# sterio_mic_MCU.net
KiCad netlist of a schematic drawn in Altium Designer
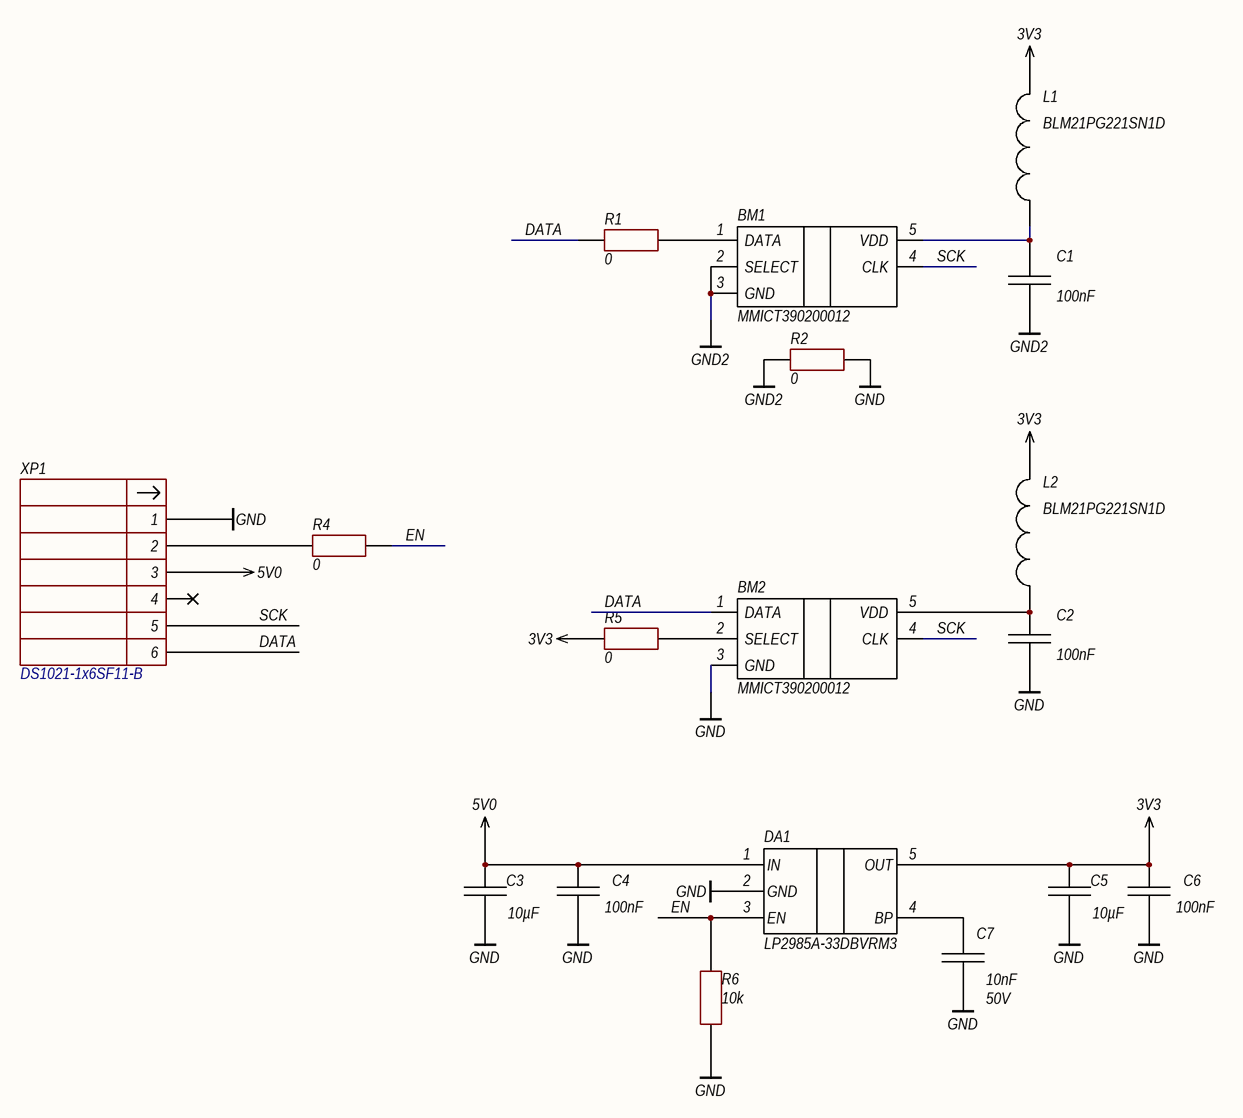
[diagram p0: sterio_mic MCU.SchDoc]

(export (version "E")
  (design (tool "Eeschema 10.0.6"))
  (components
    (comp (ref "BM1")
      (value "MMICT390200012")
      (footprint "5-Terminal LGA_CAV")
      (description "digital MEMS microphone")
      (fields (field (name "MANUFACTURER") "TDK") (field (name "AUTHOR") "t.dorakh"))
      (libsource (lib "EnCata Concord Pro") (part "MMICT390200012"))
    )
    (comp (ref "BM2")
      (value "MMICT390200012")
      (footprint "5-Terminal LGA_CAV")
      (description "digital MEMS microphone")
      (fields (field (name "MANUFACTURER") "TDK") (field (name "AUTHOR") "t.dorakh"))
      (libsource (lib "EnCata Concord Pro") (part "MMICT390200012"))
    )
    (comp (ref "C1")
      (value "CC0805KPX7R9BB104")
      (footprint "CAPC0805_H0.95_N")
      (description "0805 100nF 50V ±10% X7R")
      (fields
        (field (name "TOLERANCE") "10%")
        (field (name "CAPACITANCE") "100nF")
        (field (name "MANUFACTURER") "Yageo")
        (field (name "AUTHOR") "m.seliadtsou")
      )
      (libsource (lib "EnCata Concord Pro") (part "C"))
    )
    (comp (ref "C2")
      (value "CC0805KPX7R9BB104")
      (footprint "CAPC0805_H0.95_N")
      (description "0805 100nF 50V ±10% X7R")
      (fields
        (field (name "TOLERANCE") "10%")
        (field (name "CAPACITANCE") "100nF")
        (field (name "MANUFACTURER") "Yageo")
        (field (name "AUTHOR") "m.seliadtsou")
      )
      (libsource (lib "EnCata Concord Pro") (part "C"))
    )
    (comp (ref "C3")
      (value "CL21B106KOQNNNE")
      (footprint "CAPC0805_H1.45_N")
      (description "0805 10uF 16V ±10% X7R")
      (fields
        (field (name "CAPACITANCE") "10µF")
        (field (name "MANUFACTURER") "Samsung Electro-Mechanics")
        (field (name "TOLERANCE") "10%")
        (field (name "AUTHOR") "m.boltromeyuk")
      )
      (libsource (lib "EnCata Concord Pro") (part "C"))
    )
    (comp (ref "C4")
      (value "CC0805KPX7R9BB104")
      (footprint "CAPC0805_H0.95_N")
      (description "0805 100nF 50V ±10% X7R")
      (fields
        (field (name "TOLERANCE") "10%")
        (field (name "CAPACITANCE") "100nF")
        (field (name "MANUFACTURER") "Yageo")
        (field (name "AUTHOR") "m.seliadtsou")
      )
      (libsource (lib "EnCata Concord Pro") (part "C"))
    )
    (comp (ref "C5")
      (value "CL21B106KOQNNNE")
      (footprint "CAPC0805_H1.45_N")
      (description "0805 10uF 16V ±10% X7R")
      (fields
        (field (name "CAPACITANCE") "10µF")
        (field (name "MANUFACTURER") "Samsung Electro-Mechanics")
        (field (name "TOLERANCE") "10%")
        (field (name "AUTHOR") "m.boltromeyuk")
      )
      (libsource (lib "EnCata Concord Pro") (part "C"))
    )
    (comp (ref "C6")
      (value "CC0805KPX7R9BB104")
      (footprint "CAPC0805_H0.95_N")
      (description "0805 100nF 50V ±10% X7R")
      (fields
        (field (name "TOLERANCE") "10%")
        (field (name "CAPACITANCE") "100nF")
        (field (name "MANUFACTURER") "Yageo")
        (field (name "AUTHOR") "m.seliadtsou")
      )
      (libsource (lib "EnCata Concord Pro") (part "C"))
    )
    (comp (ref "C7")
      (value "CC0805JKNPO9BN103")
      (footprint "CAPC0805_H0.95_N")
      (description "0805 10nF 50V ±5% NP0")
      (fields
        (field (name "CAPACITANCE") "10nF")
        (field (name "MANUFACTURER") "Yageo")
        (field (name "TOLERANCE") "5%")
        (field (name "VOLTAGE RATING") "50V")
        (field (name "AUTHOR") "v.ivanchenko")
      )
      (libsource (lib "EnCata Concord Pro") (part "C"))
    )
    (comp (ref "DA1")
      (value "LP2985A-33DBVRM3")
      (footprint "SOT-23-5")
      (description "150-mA 16-V low-dropout (LDO) voltage regulator with high-accuracy 5-SOT-23 -40 to 125")
      (fields (field (name "MANUFACTURER") "Texas Instruments") (field (name "AUTHOR") "i.auramchyk"))
      (libsource (lib "EnCata Concord Pro") (part "LP2985A"))
    )
    (comp (ref "L1")
      (value "BLM21PG221SN1D")
      (footprint "INDC0805_H1.25_N")
      (description "9mΩ ±25% 22Ω@100MHz 6A 0805 Ferrite Beads ROHS")
      (fields
        (field (name "MANUFACTURER") "Murata Electronics")
        (field (name "MANUFACTURER PART NUMBER") "BLM21PG220SN1D")
        (field (name "AUTHOR") "m.boltromeyuk")
      )
      (libsource (lib "EnCata Concord Pro") (part "L"))
    )
    (comp (ref "L2")
      (value "BLM21PG221SN1D")
      (footprint "INDC0805_H1.25_N")
      (description "9mΩ ±25% 22Ω@100MHz 6A 0805 Ferrite Beads ROHS")
      (fields
        (field (name "MANUFACTURER") "Murata Electronics")
        (field (name "MANUFACTURER PART NUMBER") "BLM21PG220SN1D")
        (field (name "AUTHOR") "m.boltromeyuk")
      )
      (libsource (lib "EnCata Concord Pro") (part "L"))
    )
    (comp (ref "R1")
      (value "RC0805FR-070RL")
      (footprint "RESC0805_N")
      (description "RES SMD 0 OHM JUMPER 1% 1/8W 0805")
      (fields
        (field (name "MANUFACTURER") "Yageo")
        (field (name "RESISTANCE") "0")
        (field (name "TOLERANCE") "1%")
        (field (name "AUTHOR") "M.S. Koval")
      )
      (libsource (lib "") (part "R_GENERAL_2"))
    )
    (comp (ref "R2")
      (value "RC0805FR-070RL")
      (footprint "RESC0805_N")
      (description "RES SMD 0 OHM JUMPER 1% 1/8W 0805")
      (fields
        (field (name "MANUFACTURER") "Yageo")
        (field (name "RESISTANCE") "0")
        (field (name "TOLERANCE") "1%")
        (field (name "AUTHOR") "M.S. Koval")
      )
      (libsource (lib "EnCata Concord Pro") (part "R_GENERAL"))
    )
    (comp (ref "R4")
      (value "RC0805FR-070RL")
      (footprint "RESC0805_N")
      (description "RES SMD 0 OHM JUMPER 1% 1/8W 0805")
      (fields
        (field (name "MANUFACTURER") "Yageo")
        (field (name "RESISTANCE") "0")
        (field (name "TOLERANCE") "1%")
        (field (name "AUTHOR") "M.S. Koval")
      )
      (libsource (lib "EnCata Concord Pro") (part "R_GENERAL"))
    )
    (comp (ref "R5")
      (value "RC0805FR-070RL")
      (footprint "RESC0805_N")
      (description "RES SMD 0 OHM JUMPER 1% 1/8W 0805")
      (fields
        (field (name "MANUFACTURER") "Yageo")
        (field (name "RESISTANCE") "0")
        (field (name "TOLERANCE") "1%")
        (field (name "AUTHOR") "M.S. Koval")
      )
      (libsource (lib "") (part "R_GENERAL_2"))
    )
    (comp (ref "R6")
      (value "RT0805BRB0710KL")
      (footprint "RESC0805_N")
      (description "RES SMD 10 KOHM 0.1% 1/8W 0805  10ppm")
      (fields
        (field (name "MANUFACTURER") "Yageo")
        (field (name "RESISTANCE") "10k")
        (field (name "TOLERANCE") "0.1%")
        (field (name "AUTHOR") "u.sushko")
      )
      (libsource (lib "") (part "R_GENERAL_1"))
    )
    (comp (ref "XP1")
      (value "DS1021-1x6SF11-B")
      (footprint "PLS-6(DS-1021-1x6)")
      (description "2.54mm, 6 pin, Male, 3A, Vertical mounting, CONNFLY")
      (fields (field (name "MANUFACTURER") "CONNFLY") (field (name "AUTHOR") "a.antipov"))
      (libsource (lib "EnCata Concord Pro") (part "XP6"))
    )
  )
  (nets
    (net (code "1") (name "/DATA") (class "Default")
      (node (ref "BM2") (pin "1") (pinfunction "DATA_1") (pintype "passive"))
      (node (ref "R1") (pin "1") (pinfunction "1_1") (pintype "passive"))
      (node (ref "XP1") (pin "6") (pinfunction "6_6") (pintype "passive"))
    )
    (net (code "2") (name "/EN") (class "Default")
      (node (ref "DA1") (pin "3") (pinfunction "EN_3") (pintype "passive"))
      (node (ref "R4") (pin "1") (pinfunction "1_1") (pintype "passive"))
      (node (ref "R6") (pin "2") (pinfunction "2_2") (pintype "passive"))
    )
    (net (code "3") (name "/SCK") (class "Default")
      (node (ref "BM1") (pin "4") (pinfunction "CLK_4") (pintype "passive"))
      (node (ref "BM2") (pin "4") (pinfunction "CLK_4") (pintype "passive"))
      (node (ref "XP1") (pin "5") (pinfunction "5_5") (pintype "passive"))
    )
    (net (code "4") (name "3V3") (class "Default")
      (node (ref "C5") (pin "1") (pinfunction "1_1") (pintype "passive"))
      (node (ref "C6") (pin "1") (pinfunction "1_1") (pintype "passive"))
      (node (ref "DA1") (pin "5") (pinfunction "OUT_5") (pintype "power_in"))
      (node (ref "L1") (pin "2") (pinfunction "2_2") (pintype "passive"))
      (node (ref "L2") (pin "2") (pinfunction "2_2") (pintype "passive"))
      (node (ref "R5") (pin "1") (pinfunction "1_1") (pintype "passive"))
    )
    (net (code "5") (name "5V0") (class "Default")
      (node (ref "C3") (pin "1") (pinfunction "1_1") (pintype "passive"))
      (node (ref "C4") (pin "1") (pinfunction "1_1") (pintype "passive"))
      (node (ref "DA1") (pin "1") (pinfunction "IN_1") (pintype "power_in"))
      (node (ref "XP1") (pin "3") (pinfunction "3_3") (pintype "passive"))
    )
    (net (code "6") (name "GND") (class "Default")
      (node (ref "BM2") (pin "3") (pinfunction "GND_3") (pintype "passive"))
      (node (ref "C2") (pin "2") (pinfunction "2_2") (pintype "passive"))
      (node (ref "C3") (pin "2") (pinfunction "2_2") (pintype "passive"))
      (node (ref "C4") (pin "2") (pinfunction "2_2") (pintype "passive"))
      (node (ref "C5") (pin "2") (pinfunction "2_2") (pintype "passive"))
      (node (ref "C6") (pin "2") (pinfunction "2_2") (pintype "passive"))
      (node (ref "C7") (pin "2") (pinfunction "2_2") (pintype "passive"))
      (node (ref "DA1") (pin "2") (pinfunction "GND_2") (pintype "passive"))
      (node (ref "R2") (pin "1") (pinfunction "1_1") (pintype "passive"))
      (node (ref "R6") (pin "1") (pinfunction "1_1") (pintype "passive"))
      (node (ref "XP1") (pin "1") (pinfunction "1_1") (pintype "passive"))
    )
    (net (code "7") (name "GND2") (class "Default")
      (node (ref "BM1") (pin "2") (pinfunction "SELECT_2") (pintype "passive"))
      (node (ref "BM1") (pin "3") (pinfunction "GND_3") (pintype "passive"))
      (node (ref "C1") (pin "2") (pinfunction "2_2") (pintype "passive"))
      (node (ref "R2") (pin "2") (pinfunction "2_2") (pintype "passive"))
    )
    (net (code "8") (name "Net-(BM1-DATA)") (class "Default")
      (node (ref "BM1") (pin "1") (pinfunction "DATA_1") (pintype "passive"))
      (node (ref "R1") (pin "2") (pinfunction "2_2") (pintype "passive"))
    )
    (net (code "9") (name "Net-(BM1-VDD)") (class "Default")
      (node (ref "BM1") (pin "5") (pinfunction "VDD_5") (pintype "passive"))
      (node (ref "C1") (pin "1") (pinfunction "1_1") (pintype "passive"))
      (node (ref "L1") (pin "1") (pinfunction "1_1") (pintype "passive"))
    )
    (net (code "10") (name "Net-(BM2-SELECT)") (class "Default")
      (node (ref "BM2") (pin "2") (pinfunction "SELECT_2") (pintype "passive"))
      (node (ref "R5") (pin "2") (pinfunction "2_2") (pintype "passive"))
    )
    (net (code "11") (name "Net-(BM2-VDD)") (class "Default")
      (node (ref "BM2") (pin "5") (pinfunction "VDD_5") (pintype "passive"))
      (node (ref "C2") (pin "1") (pinfunction "1_1") (pintype "passive"))
      (node (ref "L2") (pin "1") (pinfunction "1_1") (pintype "passive"))
    )
    (net (code "12") (name "Net-(DA1-BP)") (class "Default")
      (node (ref "C7") (pin "1") (pinfunction "1_1") (pintype "passive"))
      (node (ref "DA1") (pin "4") (pinfunction "BP_4") (pintype "passive"))
    )
    (net (code "13") (name "Net-(R4-Pad2)") (class "Default")
      (node (ref "R4") (pin "2") (pinfunction "2_2") (pintype "passive"))
      (node (ref "XP1") (pin "2") (pinfunction "2_2") (pintype "passive"))
    )
    (net (code "14") (name "unconnected-(XP1-Pad4)") (class "Default")
      (node (ref "XP1") (pin "4") (pinfunction "4_4") (pintype "passive+no_connect"))
    )
  )
)
